# console.net
KiCad netlist of a schematic drawn in EAGLE
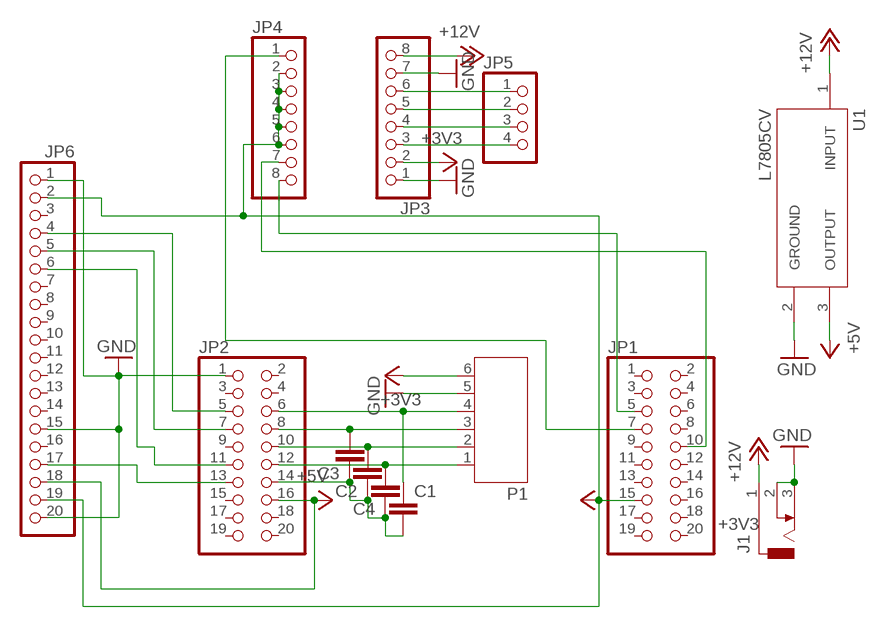
[diagram p0: schematic, sheet 1]

(export (version "E")
  (design (tool "Eeschema 10.0.6"))
  (components
    (comp (ref "C1")
      (value "C-EU025-030X050")
      (footprint "eagle-import:C025-030X050")
      (libsource (lib "eagle-import") (part "C-EU025-030X050"))
    )
    (comp (ref "C2")
      (value "C-EU025-030X050")
      (footprint "eagle-import:C025-030X050")
      (libsource (lib "eagle-import") (part "C-EU025-030X050"))
    )
    (comp (ref "C3")
      (value "C-EU025-030X050")
      (footprint "eagle-import:C025-030X050")
      (libsource (lib "eagle-import") (part "C-EU025-030X050"))
    )
    (comp (ref "C4")
      (value "C-EU025-030X050")
      (footprint "eagle-import:C025-030X050")
      (libsource (lib "eagle-import") (part "C-EU025-030X050"))
    )
    (comp (ref "J1")
      (value "DCJ0303")
      (footprint "eagle-import:DCJ0303")
      (libsource (lib "eagle-import") (part "DCJ0303"))
    )
    (comp (ref "JP1")
      (value "PINHD-2X10")
      (footprint "eagle-import:2X10")
      (libsource (lib "eagle-import") (part "PINHD-2X10"))
    )
    (comp (ref "JP2")
      (value "PINHD-2X10")
      (footprint "eagle-import:2X10")
      (libsource (lib "eagle-import") (part "PINHD-2X10"))
    )
    (comp (ref "JP3")
      (value "PINHD-1X8")
      (footprint "eagle-import:1X08")
      (libsource (lib "eagle-import") (part "PINHD-1X8"))
    )
    (comp (ref "JP4")
      (value "PINHD-1X8")
      (footprint "eagle-import:1X08")
      (libsource (lib "eagle-import") (part "PINHD-1X8"))
    )
    (comp (ref "JP5")
      (value "PINHD-1X4/90")
      (footprint "eagle-import:1X04_90")
      (libsource (lib "eagle-import") (part "PINHD-1X4/90"))
    )
    (comp (ref "JP6")
      (value "PINHD-1X20")
      (footprint "eagle-import:1X20")
      (libsource (lib "eagle-import") (part "PINHD-1X20"))
    )
    (comp (ref "P1")
      (value "JST-PH6")
      (footprint "eagle-import:JST-PH6")
      (libsource (lib "eagle-import") (part "JST-PH6"))
    )
    (comp (ref "U1")
      (value "L7805CV")
      (footprint "eagle-import:TO255P1040X460X1968-3")
      (fields (field (name "MF") "STMicroelectronics"))
      (libsource (lib "eagle-import") (part "L7805CV"))
    )
  )
  (nets
    (net (code "1") (name "+3V3") (class "Default")
      (node (ref "JP1") (pin "15") (pinfunction "15_15") (pintype "passive"))
      (node (ref "JP3") (pin "2") (pinfunction "2_2") (pintype "passive"))
      (node (ref "JP4") (pin "2") (pinfunction "2_2") (pintype "passive"))
      (node (ref "JP4") (pin "3") (pinfunction "3_3") (pintype "passive"))
      (node (ref "JP4") (pin "4") (pinfunction "4_4") (pintype "passive"))
      (node (ref "JP4") (pin "5") (pinfunction "5_5") (pintype "passive"))
      (node (ref "JP4") (pin "6") (pinfunction "6_6") (pintype "passive"))
      (node (ref "JP6") (pin "19") (pinfunction "19_19") (pintype "passive"))
      (node (ref "JP6") (pin "2") (pinfunction "2_2") (pintype "passive"))
      (node (ref "P1") (pin "6") (pinfunction "6_6") (pintype "passive"))
    )
    (net (code "2") (name "+5V") (class "Default")
      (node (ref "JP2") (pin "16") (pinfunction "16_16") (pintype "passive"))
      (node (ref "JP6") (pin "18") (pinfunction "18_18") (pintype "passive"))
      (node (ref "U1") (pin "3") (pinfunction "OUTPUT_3") (pintype "output"))
    )
    (net (code "3") (name "+12V") (class "Default")
      (node (ref "J1") (pin "1") (pinfunction "1_1") (pintype "passive"))
      (node (ref "JP3") (pin "8") (pinfunction "8_8") (pintype "passive"))
      (node (ref "U1") (pin "1") (pinfunction "INPUT_1") (pintype "input"))
    )
    (net (code "4") (name "GND") (class "Default")
      (node (ref "J1") (pin "2") (pinfunction "2_2") (pintype "passive"))
      (node (ref "J1") (pin "3") (pinfunction "3_3") (pintype "passive"))
      (node (ref "JP2") (pin "1") (pinfunction "1_1") (pintype "passive"))
      (node (ref "JP3") (pin "1") (pinfunction "1_1") (pintype "passive"))
      (node (ref "JP3") (pin "7") (pinfunction "7_7") (pintype "passive"))
      (node (ref "JP6") (pin "1") (pinfunction "1_1") (pintype "passive"))
      (node (ref "JP6") (pin "15") (pinfunction "15_15") (pintype "passive"))
      (node (ref "JP6") (pin "20") (pinfunction "20_20") (pintype "passive"))
      (node (ref "P1") (pin "5") (pinfunction "5_5") (pintype "passive"))
      (node (ref "U1") (pin "2") (pinfunction "GROUND_2") (pintype "power_in"))
    )
    (net (code "5") (name "Net-(C1-Pad1)") (class "Default")
      (node (ref "C1") (pin "1") (pinfunction "1_1") (pintype "passive"))
      (node (ref "JP2") (pin "6") (pinfunction "6_6") (pintype "passive"))
      (node (ref "P1") (pin "4") (pinfunction "4_4") (pintype "passive"))
    )
    (net (code "6") (name "Net-(C1-Pad2)") (class "Default")
      (node (ref "C1") (pin "2") (pinfunction "2_2") (pintype "passive"))
      (node (ref "C2") (pin "1") (pinfunction "1_1") (pintype "passive"))
      (node (ref "C3") (pin "1") (pinfunction "1_1") (pintype "passive"))
      (node (ref "C4") (pin "1") (pinfunction "1_1") (pintype "passive"))
      (node (ref "JP2") (pin "14") (pinfunction "14_14") (pintype "passive"))
    )
    (net (code "7") (name "Net-(C2-Pad2)") (class "Default")
      (node (ref "C2") (pin "2") (pinfunction "2_2") (pintype "passive"))
      (node (ref "JP2") (pin "10") (pinfunction "10_10") (pintype "passive"))
      (node (ref "P1") (pin "2") (pinfunction "2_2") (pintype "passive"))
    )
    (net (code "8") (name "Net-(C3-Pad2)") (class "Default")
      (node (ref "C3") (pin "2") (pinfunction "2_2") (pintype "passive"))
      (node (ref "JP2") (pin "8") (pinfunction "8_8") (pintype "passive"))
      (node (ref "P1") (pin "3") (pinfunction "3_3") (pintype "passive"))
    )
    (net (code "9") (name "Net-(C4-Pad2)") (class "Default")
      (node (ref "C4") (pin "2") (pinfunction "2_2") (pintype "passive"))
      (node (ref "JP2") (pin "12") (pinfunction "12_12") (pintype "passive"))
      (node (ref "P1") (pin "1") (pinfunction "1_1") (pintype "passive"))
    )
    (net (code "10") (name "Net-(JP1-Pad5)") (class "Default")
      (node (ref "JP1") (pin "5") (pinfunction "5_5") (pintype "passive"))
      (node (ref "JP4") (pin "8") (pinfunction "8_8") (pintype "passive"))
    )
    (net (code "11") (name "Net-(JP1-Pad7)") (class "Default")
      (node (ref "JP1") (pin "7") (pinfunction "7_7") (pintype "passive"))
      (node (ref "JP4") (pin "1") (pinfunction "1_1") (pintype "passive"))
    )
    (net (code "12") (name "Net-(JP1-Pad10)") (class "Default")
      (node (ref "JP1") (pin "10") (pinfunction "10_10") (pintype "passive"))
      (node (ref "JP4") (pin "7") (pinfunction "7_7") (pintype "passive"))
    )
    (net (code "13") (name "Net-(JP2-Pad5)") (class "Default")
      (node (ref "JP2") (pin "5") (pinfunction "5_5") (pintype "passive"))
      (node (ref "JP6") (pin "4") (pinfunction "4_4") (pintype "passive"))
    )
    (net (code "14") (name "Net-(JP2-Pad7)") (class "Default")
      (node (ref "JP2") (pin "7") (pinfunction "7_7") (pintype "passive"))
      (node (ref "JP6") (pin "5") (pinfunction "5_5") (pintype "passive"))
    )
    (net (code "15") (name "Net-(JP2-Pad11)") (class "Default")
      (node (ref "JP2") (pin "11") (pinfunction "11_11") (pintype "passive"))
      (node (ref "JP6") (pin "6") (pinfunction "6_6") (pintype "passive"))
    )
    (net (code "16") (name "Net-(JP2-Pad13)") (class "Default")
      (node (ref "JP2") (pin "13") (pinfunction "13_13") (pintype "passive"))
      (node (ref "JP6") (pin "17") (pinfunction "17_17") (pintype "passive"))
    )
    (net (code "17") (name "Net-(JP3-Pad3)") (class "Default")
      (node (ref "JP3") (pin "3") (pinfunction "3_3") (pintype "passive"))
      (node (ref "JP5") (pin "4") (pinfunction "4_4") (pintype "passive"))
    )
    (net (code "18") (name "Net-(JP3-Pad4)") (class "Default")
      (node (ref "JP3") (pin "4") (pinfunction "4_4") (pintype "passive"))
      (node (ref "JP5") (pin "3") (pinfunction "3_3") (pintype "passive"))
    )
    (net (code "19") (name "Net-(JP3-Pad5)") (class "Default")
      (node (ref "JP3") (pin "5") (pinfunction "5_5") (pintype "passive"))
      (node (ref "JP5") (pin "2") (pinfunction "2_2") (pintype "passive"))
    )
    (net (code "20") (name "Net-(JP3-Pad6)") (class "Default")
      (node (ref "JP3") (pin "6") (pinfunction "6_6") (pintype "passive"))
      (node (ref "JP5") (pin "1") (pinfunction "1_1") (pintype "passive"))
    )
    (net (code "21") (name "unconnected-(JP1-Pad1)") (class "Default")
      (node (ref "JP1") (pin "1") (pinfunction "1_1") (pintype "passive"))
    )
    (net (code "22") (name "unconnected-(JP1-Pad2)") (class "Default")
      (node (ref "JP1") (pin "2") (pinfunction "2_2") (pintype "passive"))
    )
    (net (code "23") (name "unconnected-(JP1-Pad3)") (class "Default")
      (node (ref "JP1") (pin "3") (pinfunction "3_3") (pintype "passive"))
    )
    (net (code "24") (name "unconnected-(JP1-Pad4)") (class "Default")
      (node (ref "JP1") (pin "4") (pinfunction "4_4") (pintype "passive"))
    )
    (net (code "25") (name "unconnected-(JP1-Pad6)") (class "Default")
      (node (ref "JP1") (pin "6") (pinfunction "6_6") (pintype "passive"))
    )
    (net (code "26") (name "unconnected-(JP1-Pad8)") (class "Default")
      (node (ref "JP1") (pin "8") (pinfunction "8_8") (pintype "passive"))
    )
    (net (code "27") (name "unconnected-(JP1-Pad9)") (class "Default")
      (node (ref "JP1") (pin "9") (pinfunction "9_9") (pintype "passive"))
    )
    (net (code "28") (name "unconnected-(JP1-Pad11)") (class "Default")
      (node (ref "JP1") (pin "11") (pinfunction "11_11") (pintype "passive"))
    )
    (net (code "29") (name "unconnected-(JP1-Pad12)") (class "Default")
      (node (ref "JP1") (pin "12") (pinfunction "12_12") (pintype "passive"))
    )
    (net (code "30") (name "unconnected-(JP1-Pad13)") (class "Default")
      (node (ref "JP1") (pin "13") (pinfunction "13_13") (pintype "passive"))
    )
    (net (code "31") (name "unconnected-(JP1-Pad14)") (class "Default")
      (node (ref "JP1") (pin "14") (pinfunction "14_14") (pintype "passive"))
    )
    (net (code "32") (name "unconnected-(JP1-Pad16)") (class "Default")
      (node (ref "JP1") (pin "16") (pinfunction "16_16") (pintype "passive"))
    )
    (net (code "33") (name "unconnected-(JP1-Pad17)") (class "Default")
      (node (ref "JP1") (pin "17") (pinfunction "17_17") (pintype "passive"))
    )
    (net (code "34") (name "unconnected-(JP1-Pad18)") (class "Default")
      (node (ref "JP1") (pin "18") (pinfunction "18_18") (pintype "passive"))
    )
    (net (code "35") (name "unconnected-(JP1-Pad19)") (class "Default")
      (node (ref "JP1") (pin "19") (pinfunction "19_19") (pintype "passive"))
    )
    (net (code "36") (name "unconnected-(JP1-Pad20)") (class "Default")
      (node (ref "JP1") (pin "20") (pinfunction "20_20") (pintype "passive"))
    )
    (net (code "37") (name "unconnected-(JP2-Pad2)") (class "Default")
      (node (ref "JP2") (pin "2") (pinfunction "2_2") (pintype "passive"))
    )
    (net (code "38") (name "unconnected-(JP2-Pad3)") (class "Default")
      (node (ref "JP2") (pin "3") (pinfunction "3_3") (pintype "passive"))
    )
    (net (code "39") (name "unconnected-(JP2-Pad4)") (class "Default")
      (node (ref "JP2") (pin "4") (pinfunction "4_4") (pintype "passive"))
    )
    (net (code "40") (name "unconnected-(JP2-Pad9)") (class "Default")
      (node (ref "JP2") (pin "9") (pinfunction "9_9") (pintype "passive"))
    )
    (net (code "41") (name "unconnected-(JP2-Pad15)") (class "Default")
      (node (ref "JP2") (pin "15") (pinfunction "15_15") (pintype "passive"))
    )
    (net (code "42") (name "unconnected-(JP2-Pad17)") (class "Default")
      (node (ref "JP2") (pin "17") (pinfunction "17_17") (pintype "passive"))
    )
    (net (code "43") (name "unconnected-(JP2-Pad18)") (class "Default")
      (node (ref "JP2") (pin "18") (pinfunction "18_18") (pintype "passive"))
    )
    (net (code "44") (name "unconnected-(JP2-Pad19)") (class "Default")
      (node (ref "JP2") (pin "19") (pinfunction "19_19") (pintype "passive"))
    )
    (net (code "45") (name "unconnected-(JP2-Pad20)") (class "Default")
      (node (ref "JP2") (pin "20") (pinfunction "20_20") (pintype "passive"))
    )
    (net (code "46") (name "unconnected-(JP6-Pad3)") (class "Default")
      (node (ref "JP6") (pin "3") (pinfunction "3_3") (pintype "passive"))
    )
    (net (code "47") (name "unconnected-(JP6-Pad7)") (class "Default")
      (node (ref "JP6") (pin "7") (pinfunction "7_7") (pintype "passive"))
    )
    (net (code "48") (name "unconnected-(JP6-Pad8)") (class "Default")
      (node (ref "JP6") (pin "8") (pinfunction "8_8") (pintype "passive"))
    )
    (net (code "49") (name "unconnected-(JP6-Pad9)") (class "Default")
      (node (ref "JP6") (pin "9") (pinfunction "9_9") (pintype "passive"))
    )
    (net (code "50") (name "unconnected-(JP6-Pad10)") (class "Default")
      (node (ref "JP6") (pin "10") (pinfunction "10_10") (pintype "passive"))
    )
    (net (code "51") (name "unconnected-(JP6-Pad11)") (class "Default")
      (node (ref "JP6") (pin "11") (pinfunction "11_11") (pintype "passive"))
    )
    (net (code "52") (name "unconnected-(JP6-Pad12)") (class "Default")
      (node (ref "JP6") (pin "12") (pinfunction "12_12") (pintype "passive"))
    )
    (net (code "53") (name "unconnected-(JP6-Pad13)") (class "Default")
      (node (ref "JP6") (pin "13") (pinfunction "13_13") (pintype "passive"))
    )
    (net (code "54") (name "unconnected-(JP6-Pad14)") (class "Default")
      (node (ref "JP6") (pin "14") (pinfunction "14_14") (pintype "passive"))
    )
    (net (code "55") (name "unconnected-(JP6-Pad16)") (class "Default")
      (node (ref "JP6") (pin "16") (pinfunction "16_16") (pintype "passive"))
    )
  )
)
